# 347.net
KiCad netlist of a schematic drawn in Altium Designer
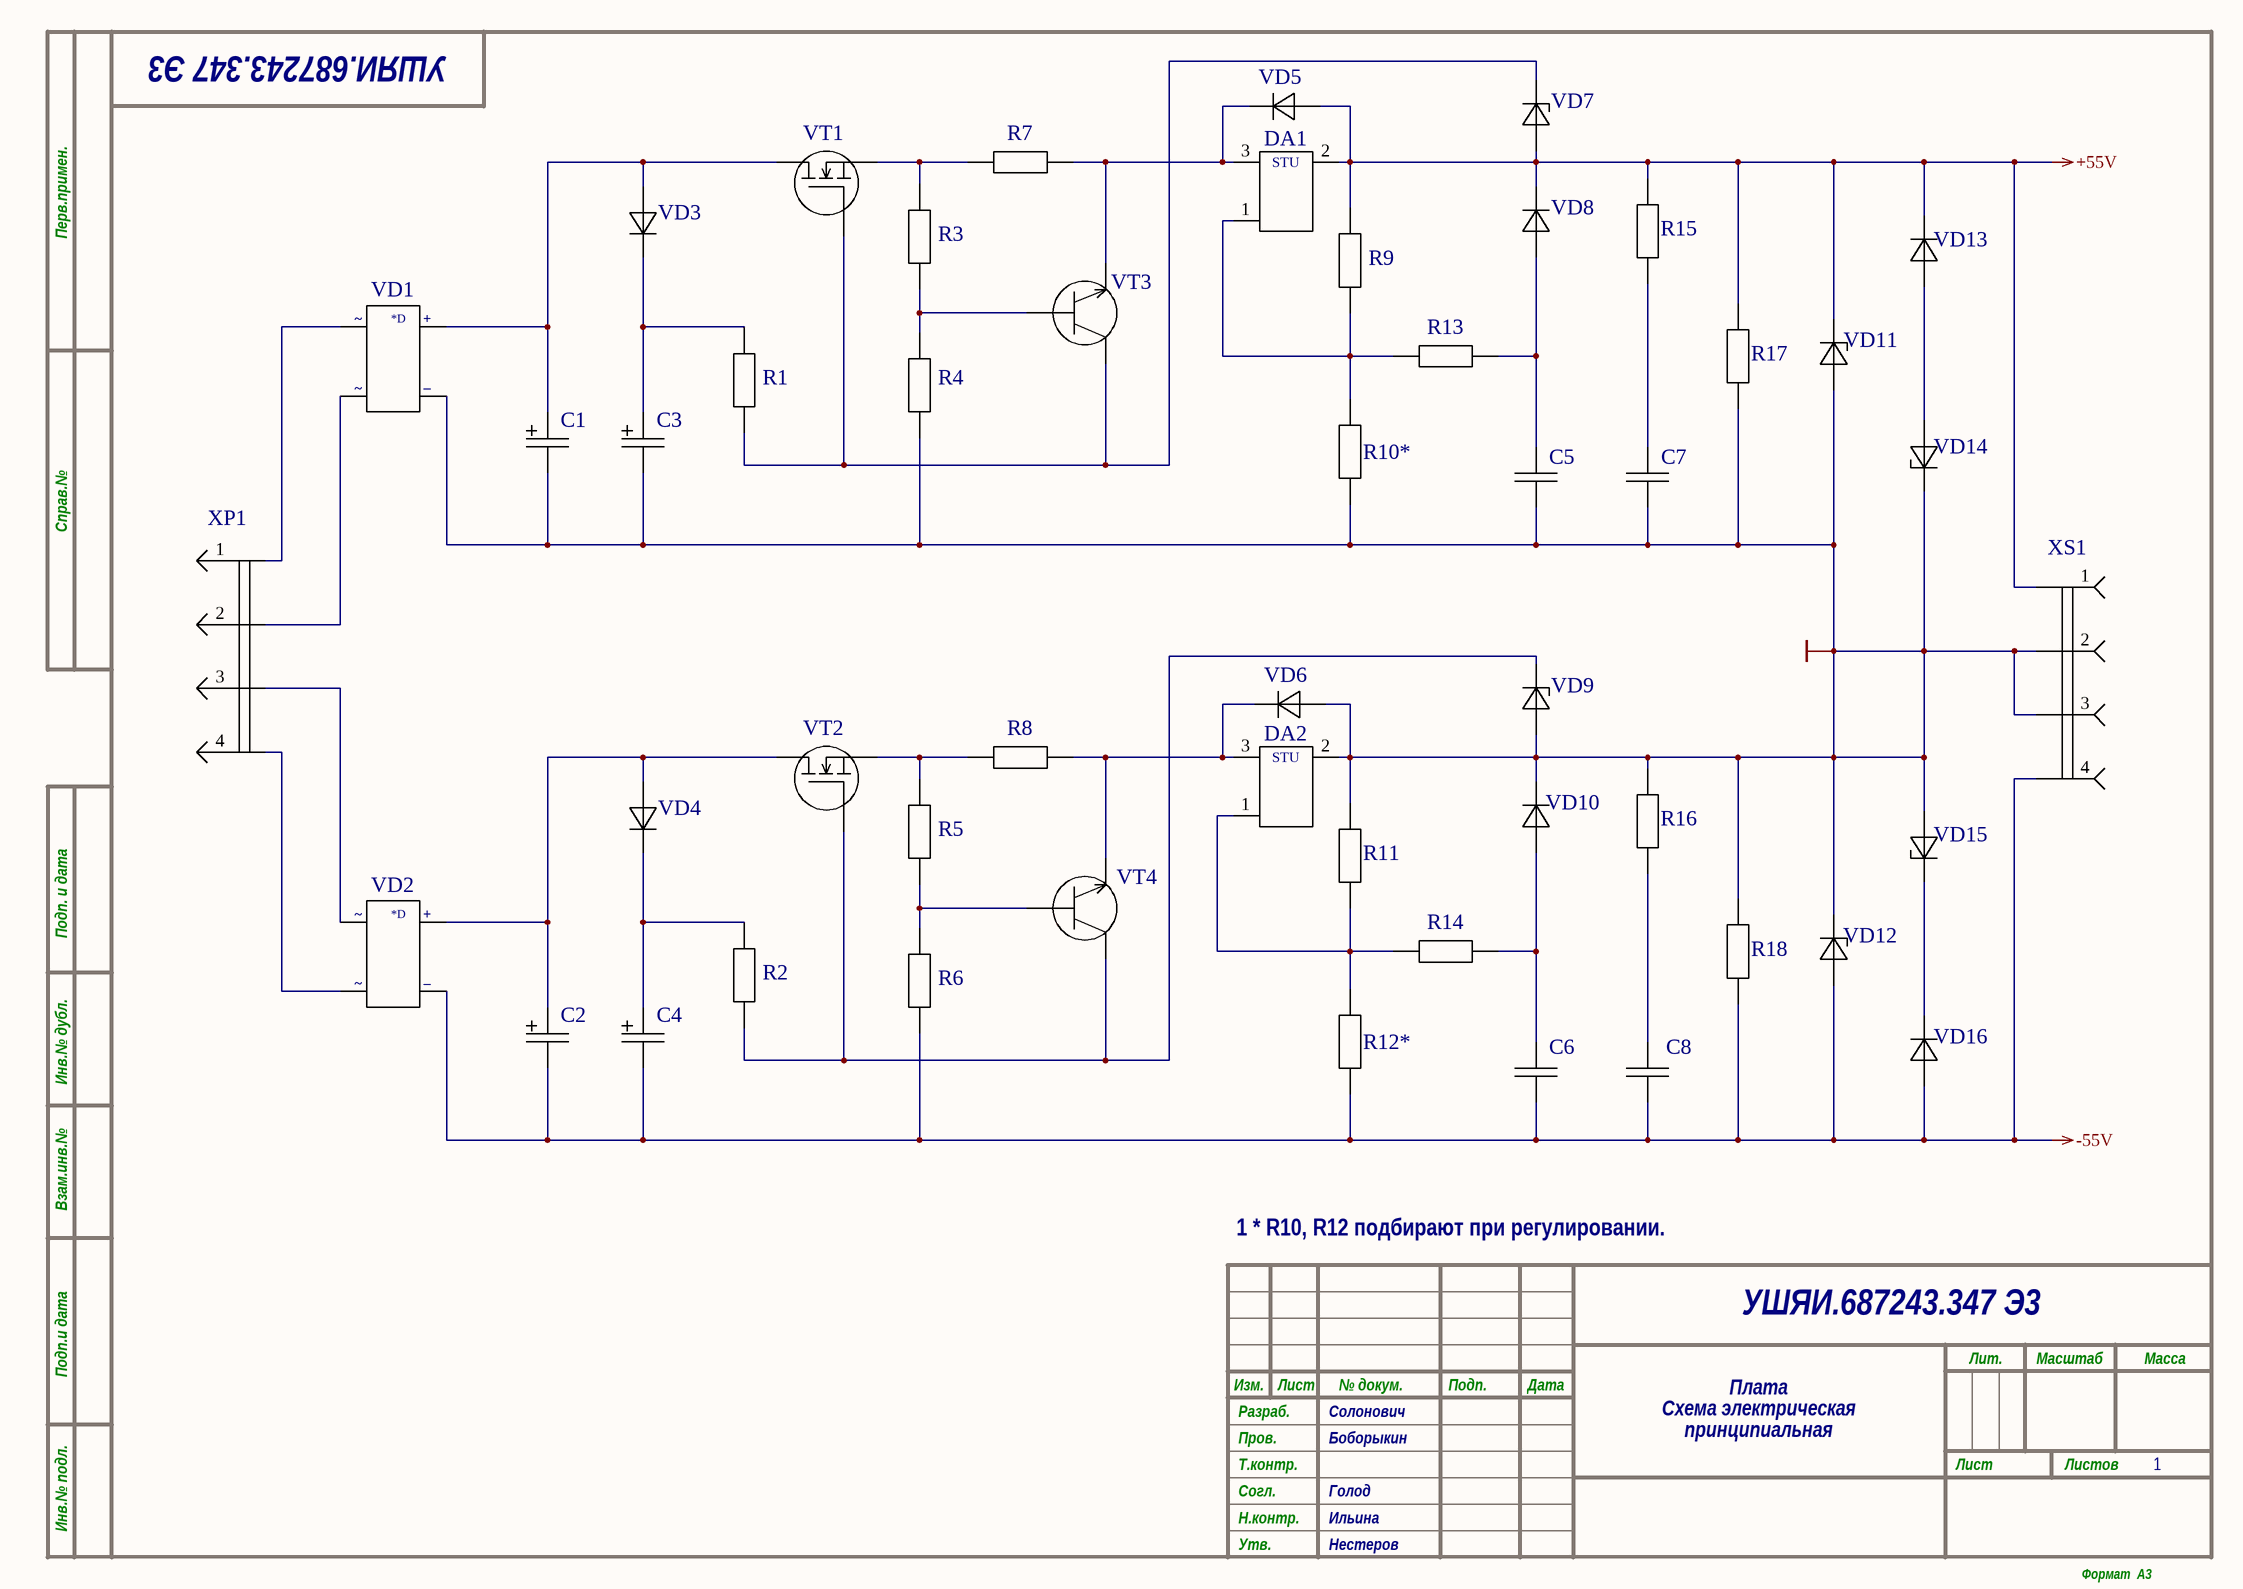
[diagram p0: Плата 347.SchDoc]

(export (version "E")
  (design (tool "Eeschema 10.0.6"))
  (components
    (comp (ref "C1") (value "Полярный конденсатор") (libsource (lib "Schlib1") (part "Полярный конденсатор")))
    (comp (ref "C2") (value "Полярный конденсатор") (libsource (lib "Schlib1") (part "Полярный конденсатор")))
    (comp (ref "C3") (value "Полярный конденсатор") (libsource (lib "Schlib1") (part "Полярный конденсатор")))
    (comp (ref "C4") (value "Полярный конденсатор") (libsource (lib "Schlib1") (part "Полярный конденсатор")))
    (comp (ref "C5") (value "Конденсатор") (libsource (lib "Schlib1") (part "Конденсатор")))
    (comp (ref "C6") (value "Конденсатор") (libsource (lib "Schlib1") (part "Конденсатор")))
    (comp (ref "C7") (value "Конденсатор") (libsource (lib "Schlib1") (part "Конденсатор")))
    (comp (ref "C8") (value "Конденсатор") (libsource (lib "Schlib1") (part "Конденсатор")))
    (comp (ref "DA1") (value "Микросхема") (libsource (lib "Schlib1") (part "Микросхема")))
    (comp (ref "DA2") (value "Микросхема") (libsource (lib "Schlib1") (part "Микросхема")))
    (comp (ref "R1") (value "Резистор") (libsource (lib "Schlib1") (part "Резистор")))
    (comp (ref "R2") (value "Резистор") (libsource (lib "Schlib1") (part "Резистор")))
    (comp (ref "R3") (value "Резистор") (libsource (lib "Schlib1") (part "Резистор")))
    (comp (ref "R4") (value "Резистор") (libsource (lib "Schlib1") (part "Резистор")))
    (comp (ref "R5") (value "Резистор") (libsource (lib "Schlib1") (part "Резистор")))
    (comp (ref "R6") (value "Резистор") (libsource (lib "Schlib1") (part "Резистор")))
    (comp (ref "R7") (value "Резистор") (libsource (lib "Schlib1") (part "Резистор")))
    (comp (ref "R8") (value "Резистор") (libsource (lib "Schlib1") (part "Резистор")))
    (comp (ref "R9") (value "Резистор") (libsource (lib "Schlib1") (part "Резистор")))
    (comp (ref "R10*") (value "Резистор") (libsource (lib "Schlib1") (part "Резистор")))
    (comp (ref "R11") (value "Резистор") (libsource (lib "Schlib1") (part "Резистор")))
    (comp (ref "R12*") (value "Резистор") (libsource (lib "Schlib1") (part "Резистор")))
    (comp (ref "R13") (value "Резистор") (libsource (lib "Schlib1") (part "Резистор")))
    (comp (ref "R14") (value "Резистор") (libsource (lib "Schlib1") (part "Резистор")))
    (comp (ref "R15") (value "Резистор") (libsource (lib "Schlib1") (part "Резистор")))
    (comp (ref "R16") (value "Резистор") (libsource (lib "Schlib1") (part "Резистор")))
    (comp (ref "R17") (value "Резистор") (libsource (lib "Schlib1") (part "Резистор")))
    (comp (ref "R18") (value "Резистор") (libsource (lib "Schlib1") (part "Резистор")))
    (comp (ref "VD1") (value "Диодный мост") (libsource (lib "Schlib1") (part "Диодный мост")))
    (comp (ref "VD2") (value "Диодный мост") (libsource (lib "Schlib1") (part "Диодный мост")))
    (comp (ref "VD3") (value "Диод") (libsource (lib "Schlib1") (part "Диод")))
    (comp (ref "VD4") (value "Диод") (libsource (lib "Schlib1") (part "Диод")))
    (comp (ref "VD5") (value "Диод") (libsource (lib "Schlib1") (part "Диод")))
    (comp (ref "VD6") (value "Диод") (libsource (lib "Schlib1") (part "Диод")))
    (comp (ref "VD7") (value "Стабилитрон") (libsource (lib "Schlib1") (part "Стабилитрон")))
    (comp (ref "VD8") (value "Диод") (libsource (lib "Schlib1") (part "Диод")))
    (comp (ref "VD9") (value "Стабилитрон") (libsource (lib "Schlib1") (part "Стабилитрон")))
    (comp (ref "VD10") (value "Диод") (libsource (lib "Schlib1") (part "Диод")))
    (comp (ref "VD11") (value "Стабилитрон") (libsource (lib "Schlib1") (part "Стабилитрон")))
    (comp (ref "VD12") (value "Стабилитрон") (libsource (lib "Schlib1") (part "Стабилитрон")))
    (comp (ref "VD13") (value "Диод") (libsource (lib "Schlib1") (part "Диод")))
    (comp (ref "VD14") (value "Стабилитрон") (libsource (lib "Schlib1") (part "Стабилитрон")))
    (comp (ref "VD15") (value "Стабилитрон") (libsource (lib "Schlib1") (part "Стабилитрон")))
    (comp (ref "VD16") (value "Диод") (libsource (lib "Schlib1") (part "Диод")))
    (comp (ref "VT1")
      (value "Индуцированный транзистор")
      (libsource (lib "Schlib1") (part "Индуцированный транзистор"))
    )
    (comp (ref "VT2")
      (value "Индуцированный транзистор")
      (libsource (lib "Schlib1") (part "Индуцированный транзистор"))
    )
    (comp (ref "VT3") (value "Транзистор") (libsource (lib "Schlib1") (part "Транзистор")))
    (comp (ref "VT4") (value "Транзистор") (libsource (lib "Schlib1") (part "Транзистор")))
    (comp (ref "XP1") (value "Вилка 4 пин") (libsource (lib "Schlib1") (part "Вилка 4 пин")))
    (comp (ref "XS1") (value "Розетка 4 пин") (libsource (lib "Schlib1") (part "Розетка 4 пин")))
  )
  (nets
    (net (code "1") (name "+55V") (class "Default")
      (node (ref "DA1") (pin "2") (pintype "power_in"))
      (node (ref "R15") (pin "1") (pintype "power_in"))
      (node (ref "R17") (pin "1") (pintype "power_in"))
      (node (ref "R9") (pin "2") (pintype "power_in"))
      (node (ref "VD11") (pin "1") (pintype "power_in"))
      (node (ref "VD13") (pin "1") (pintype "power_in"))
      (node (ref "VD5") (pin "2") (pintype "power_in"))
      (node (ref "VD7") (pin "2") (pintype "power_in"))
      (node (ref "VD8") (pin "1") (pintype "power_in"))
      (node (ref "XS1") (pin "1") (pintype "power_in"))
    )
    (net (code "2") (name "-55V") (class "Default")
      (node (ref "C2") (pin "2") (pintype "power_in"))
      (node (ref "C4") (pin "2") (pintype "power_in"))
      (node (ref "C6") (pin "2") (pintype "power_in"))
      (node (ref "C8") (pin "1") (pintype "power_in"))
      (node (ref "R12*") (pin "1") (pintype "power_in"))
      (node (ref "R18") (pin "2") (pintype "power_in"))
      (node (ref "R6") (pin "1") (pintype "power_in"))
      (node (ref "VD12") (pin "2") (pintype "power_in"))
      (node (ref "VD16") (pin "2") (pintype "power_in"))
      (node (ref "VD2") (pin "2") (pintype "power_in"))
      (node (ref "XS1") (pin "4") (pintype "power_in"))
    )
    (net (code "3") (name "GND") (class "Default")
      (node (ref "C1") (pin "2") (pintype "power_in"))
      (node (ref "C3") (pin "2") (pintype "power_in"))
      (node (ref "C5") (pin "2") (pintype "power_in"))
      (node (ref "C7") (pin "1") (pintype "power_in"))
      (node (ref "DA2") (pin "2") (pintype "power_in"))
      (node (ref "R10*") (pin "1") (pintype "power_in"))
      (node (ref "R11") (pin "2") (pintype "power_in"))
      (node (ref "R16") (pin "1") (pintype "power_in"))
      (node (ref "R17") (pin "2") (pintype "power_in"))
      (node (ref "R18") (pin "1") (pintype "power_in"))
      (node (ref "R4") (pin "1") (pintype "power_in"))
      (node (ref "VD1") (pin "2") (pintype "power_in"))
      (node (ref "VD10") (pin "1") (pintype "power_in"))
      (node (ref "VD11") (pin "2") (pintype "power_in"))
      (node (ref "VD12") (pin "1") (pintype "power_in"))
      (node (ref "VD14") (pin "1") (pintype "power_in"))
      (node (ref "VD15") (pin "2") (pintype "power_in"))
      (node (ref "VD6") (pin "2") (pintype "power_in"))
      (node (ref "VD9") (pin "2") (pintype "power_in"))
      (node (ref "XS1") (pin "2") (pintype "power_in"))
      (node (ref "XS1") (pin "3") (pintype "power_in"))
    )
    (net (code "4") (name "Net-(C1-Pad1)") (class "Default")
      (node (ref "C1") (pin "1") (pintype "power_in"))
      (node (ref "VD1") (pin "3") (pintype "power_in"))
      (node (ref "VD3") (pin "2") (pintype "power_in"))
      (node (ref "VT1") (pin "2") (pintype "power_in"))
    )
    (net (code "5") (name "Net-(C2-Pad1)") (class "Default")
      (node (ref "C2") (pin "1") (pintype "power_in"))
      (node (ref "VD2") (pin "3") (pintype "power_in"))
      (node (ref "VD4") (pin "2") (pintype "power_in"))
      (node (ref "VT2") (pin "2") (pintype "power_in"))
    )
    (net (code "6") (name "Net-(C3-Pad1)") (class "Default")
      (node (ref "C3") (pin "1") (pintype "power_in"))
      (node (ref "R1") (pin "2") (pintype "power_in"))
      (node (ref "VD3") (pin "1") (pintype "power_in"))
    )
    (net (code "7") (name "Net-(C4-Pad1)") (class "Default")
      (node (ref "C4") (pin "1") (pintype "power_in"))
      (node (ref "R2") (pin "2") (pintype "power_in"))
      (node (ref "VD4") (pin "1") (pintype "power_in"))
    )
    (net (code "8") (name "Net-(C5-Pad1)") (class "Default")
      (node (ref "C5") (pin "1") (pintype "power_in"))
      (node (ref "R13") (pin "1") (pintype "power_in"))
      (node (ref "VD8") (pin "2") (pintype "power_in"))
    )
    (net (code "9") (name "Net-(C6-Pad1)") (class "Default")
      (node (ref "C6") (pin "1") (pintype "power_in"))
      (node (ref "R14") (pin "1") (pintype "power_in"))
      (node (ref "VD10") (pin "2") (pintype "power_in"))
    )
    (net (code "10") (name "Net-(C7-Pad2)") (class "Default")
      (node (ref "C7") (pin "2") (pintype "power_in"))
      (node (ref "R15") (pin "2") (pintype "power_in"))
    )
    (net (code "11") (name "Net-(C8-Pad2)") (class "Default")
      (node (ref "C8") (pin "2") (pintype "power_in"))
      (node (ref "R16") (pin "2") (pintype "power_in"))
    )
    (net (code "12") (name "Net-(DA1-Pad1)") (class "Default")
      (node (ref "DA1") (pin "1") (pintype "power_in"))
      (node (ref "R10*") (pin "2") (pintype "power_in"))
      (node (ref "R13") (pin "2") (pintype "power_in"))
      (node (ref "R9") (pin "1") (pintype "power_in"))
    )
    (net (code "13") (name "Net-(DA1-Pad3)") (class "Default")
      (node (ref "DA1") (pin "3") (pintype "power_in"))
      (node (ref "R7") (pin "1") (pintype "power_in"))
      (node (ref "VD5") (pin "1") (pintype "power_in"))
      (node (ref "VT3") (pin "2") (pintype "power_in"))
    )
    (net (code "14") (name "Net-(DA2-Pad1)") (class "Default")
      (node (ref "DA2") (pin "1") (pintype "power_in"))
      (node (ref "R11") (pin "1") (pintype "power_in"))
      (node (ref "R12*") (pin "2") (pintype "power_in"))
      (node (ref "R14") (pin "2") (pintype "power_in"))
    )
    (net (code "15") (name "Net-(DA2-Pad3)") (class "Default")
      (node (ref "DA2") (pin "3") (pintype "power_in"))
      (node (ref "R8") (pin "1") (pintype "power_in"))
      (node (ref "VD6") (pin "1") (pintype "power_in"))
      (node (ref "VT4") (pin "2") (pintype "power_in"))
    )
    (net (code "16") (name "Net-(R1-Pad1)") (class "Default")
      (node (ref "R1") (pin "1") (pintype "power_in"))
      (node (ref "VD7") (pin "1") (pintype "power_in"))
      (node (ref "VT1") (pin "1") (pintype "power_in"))
      (node (ref "VT3") (pin "3") (pintype "power_in"))
    )
    (net (code "17") (name "Net-(R2-Pad1)") (class "Default")
      (node (ref "R2") (pin "1") (pintype "power_in"))
      (node (ref "VD9") (pin "1") (pintype "power_in"))
      (node (ref "VT2") (pin "1") (pintype "power_in"))
      (node (ref "VT4") (pin "3") (pintype "power_in"))
    )
    (net (code "18") (name "Net-(R3-Pad1)") (class "Default")
      (node (ref "R3") (pin "1") (pintype "power_in"))
      (node (ref "R4") (pin "2") (pintype "power_in"))
      (node (ref "VT3") (pin "1") (pintype "power_in"))
    )
    (net (code "19") (name "Net-(R3-Pad2)") (class "Default")
      (node (ref "R3") (pin "2") (pintype "power_in"))
      (node (ref "R7") (pin "2") (pintype "power_in"))
      (node (ref "VT1") (pin "3") (pintype "power_in"))
    )
    (net (code "20") (name "Net-(R5-Pad1)") (class "Default")
      (node (ref "R5") (pin "1") (pintype "power_in"))
      (node (ref "R6") (pin "2") (pintype "power_in"))
      (node (ref "VT4") (pin "1") (pintype "power_in"))
    )
    (net (code "21") (name "Net-(R5-Pad2)") (class "Default")
      (node (ref "R5") (pin "2") (pintype "power_in"))
      (node (ref "R8") (pin "2") (pintype "power_in"))
      (node (ref "VT2") (pin "3") (pintype "power_in"))
    )
    (net (code "22") (name "Net-(VD1-Pad1)") (class "Default")
      (node (ref "VD1") (pin "1") (pintype "power_in"))
      (node (ref "XP1") (pin "1") (pintype "power_in"))
    )
    (net (code "23") (name "Net-(VD1-Pad3)") (class "Default")
      (node (ref "VD1") (pin "3") (pintype "power_in"))
      (node (ref "XP1") (pin "2") (pintype "power_in"))
    )
    (net (code "24") (name "Net-(VD2-Pad1)") (class "Default")
      (node (ref "VD2") (pin "1") (pintype "power_in"))
      (node (ref "XP1") (pin "3") (pintype "power_in"))
    )
    (net (code "25") (name "Net-(VD2-Pad3)") (class "Default")
      (node (ref "VD2") (pin "3") (pintype "power_in"))
      (node (ref "XP1") (pin "4") (pintype "power_in"))
    )
    (net (code "26") (name "Net-(VD13-Pad2)") (class "Default")
      (node (ref "VD13") (pin "2") (pintype "power_in"))
      (node (ref "VD14") (pin "2") (pintype "power_in"))
    )
    (net (code "27") (name "Net-(VD15-Pad1)") (class "Default")
      (node (ref "VD15") (pin "1") (pintype "power_in"))
      (node (ref "VD16") (pin "1") (pintype "power_in"))
    )
  )
)
